# Watch-It-BOTTOM.net
KiCad netlist of a schematic drawn in EAGLE
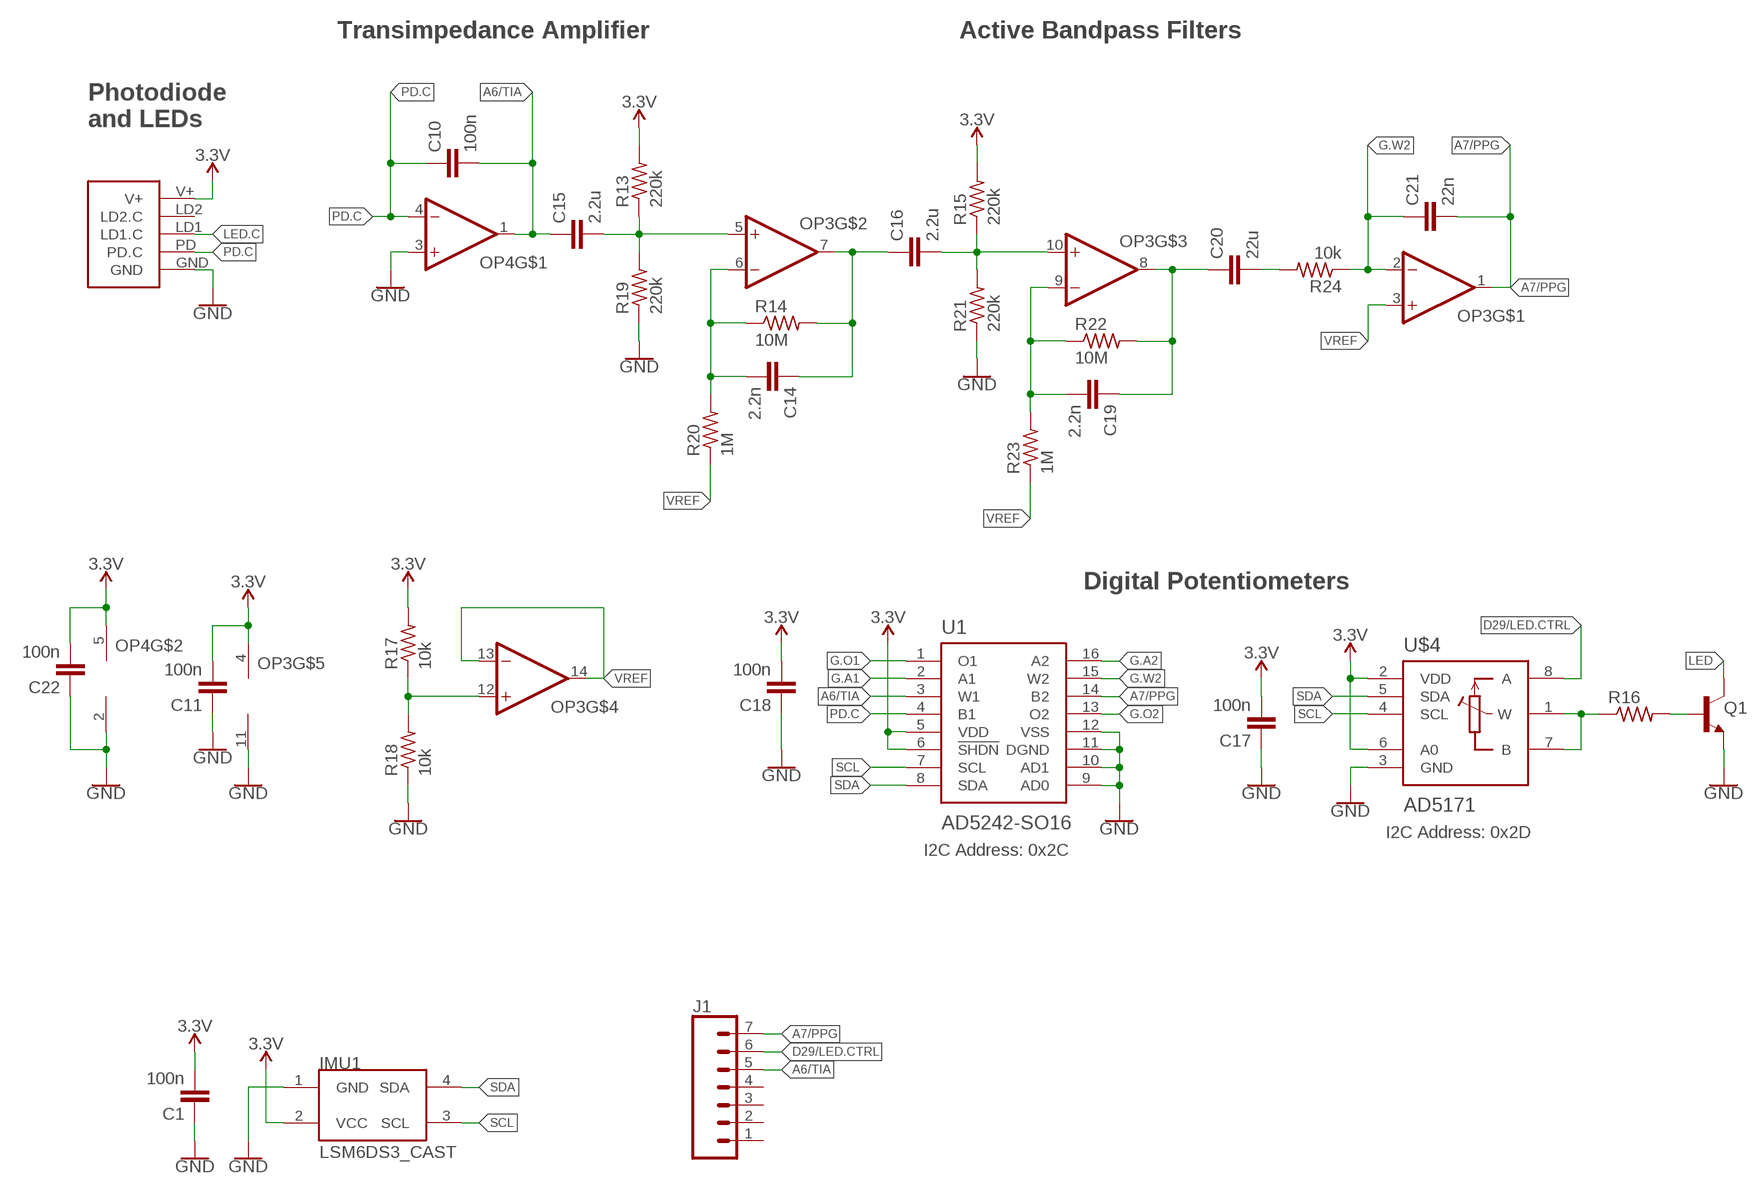
[diagram p0: schematic, sheet 1]

(export (version "E")
  (design (tool "Eeschema 10.0.6"))
  (components
    (comp (ref "C1")
      (value "100n")
      (footprint "eagle-import:C0603")
      (libsource (lib "eagle-import") (part "CAPACITOR0603"))
    )
    (comp (ref "C10")
      (value "100n")
      (footprint "eagle-import:C0603")
      (libsource (lib "eagle-import") (part "CAPACITOR0603"))
    )
    (comp (ref "C11")
      (value "100n")
      (footprint "eagle-import:C0603")
      (libsource (lib "eagle-import") (part "CAPACITOR0603"))
    )
    (comp (ref "C14")
      (value "2.2n")
      (footprint "eagle-import:C0603")
      (libsource (lib "eagle-import") (part "CAPACITOR0603"))
    )
    (comp (ref "C15")
      (value "2.2u")
      (footprint "eagle-import:C0603")
      (libsource (lib "eagle-import") (part "CAPACITOR0603"))
    )
    (comp (ref "C16")
      (value "2.2u")
      (footprint "eagle-import:C0603")
      (libsource (lib "eagle-import") (part "CAPACITOR0603"))
    )
    (comp (ref "C17")
      (value "100n")
      (footprint "eagle-import:C0603")
      (libsource (lib "eagle-import") (part "CAPACITOR0603"))
    )
    (comp (ref "C18")
      (value "100n")
      (footprint "eagle-import:C0603")
      (libsource (lib "eagle-import") (part "CAPACITOR0603"))
    )
    (comp (ref "C19")
      (value "2.2n")
      (footprint "eagle-import:C0603")
      (libsource (lib "eagle-import") (part "CAPACITOR0603"))
    )
    (comp (ref "C20")
      (value "22u")
      (footprint "eagle-import:C0603")
      (libsource (lib "eagle-import") (part "CAPACITOR0603"))
    )
    (comp (ref "C21")
      (value "22n")
      (footprint "eagle-import:C0603")
      (libsource (lib "eagle-import") (part "CAPACITOR0603"))
    )
    (comp (ref "C22")
      (value "100n")
      (footprint "eagle-import:C0603")
      (libsource (lib "eagle-import") (part "CAPACITOR0603"))
    )
    (comp (ref "IMU1")
      (value "LSM6DS3_CAST")
      (footprint "eagle-import:LSM6DS3_CAST")
      (libsource (lib "eagle-import") (part "LSM6DS3_CAST"))
    )
    (comp (ref "J1")
      (value "CONN_07")
      (footprint "eagle-import:1X07")
      (libsource (lib "eagle-import") (part "CONN_07"))
    )
    (comp (ref "OP3")
      (value "OP-QUAD-SO14")
      (footprint "eagle-import:SO14")
      (libsource (lib "eagle-import") (part "OP-QUAD-SO14"))
    )
    (comp (ref "OP4")
      (value "OP-SINGLEOT")
      (footprint "eagle-import:SOT23-5")
      (libsource (lib "eagle-import") (part "OP-SINGLEOT"))
    )
    (comp (ref "Q1")
      (value "NPN-GENERIC")
      (footprint "eagle-import:SOT23-3")
      (libsource (lib "eagle-import") (part "NPN-GENERIC"))
    )
    (comp (ref "R13")
      (value "220k")
      (footprint "eagle-import:R0603")
      (libsource (lib "eagle-import") (part "RESISTOR0603"))
    )
    (comp (ref "R14")
      (value "10M")
      (footprint "eagle-import:R0603")
      (libsource (lib "eagle-import") (part "RESISTOR0603"))
    )
    (comp (ref "R15")
      (value "220k")
      (footprint "eagle-import:R0603")
      (libsource (lib "eagle-import") (part "RESISTOR0603"))
    )
    (comp (ref "R16")
      (value "RESISTOR0603")
      (footprint "eagle-import:R0603")
      (libsource (lib "eagle-import") (part "RESISTOR0603"))
    )
    (comp (ref "R17")
      (value "10k")
      (footprint "eagle-import:R0402")
      (libsource (lib "eagle-import") (part "RESISTOR0402"))
    )
    (comp (ref "R18")
      (value "10k")
      (footprint "eagle-import:R0402")
      (libsource (lib "eagle-import") (part "RESISTOR0402"))
    )
    (comp (ref "R19")
      (value "220k")
      (footprint "eagle-import:R0603")
      (libsource (lib "eagle-import") (part "RESISTOR0603"))
    )
    (comp (ref "R20")
      (value "1M")
      (footprint "eagle-import:R0603")
      (libsource (lib "eagle-import") (part "RESISTOR0603"))
    )
    (comp (ref "R21")
      (value "220k")
      (footprint "eagle-import:R0603")
      (libsource (lib "eagle-import") (part "RESISTOR0603"))
    )
    (comp (ref "R22")
      (value "10M")
      (footprint "eagle-import:R0603")
      (libsource (lib "eagle-import") (part "RESISTOR0603"))
    )
    (comp (ref "R23")
      (value "1M")
      (footprint "eagle-import:R0603")
      (libsource (lib "eagle-import") (part "RESISTOR0603"))
    )
    (comp (ref "R24")
      (value "10k")
      (footprint "eagle-import:R0603")
      (libsource (lib "eagle-import") (part "RESISTOR0603"))
    )
    (comp (ref "U$3")
      (value "PPG.MODULE.2")
      (footprint "eagle-import:PPG.MODULE.2")
      (libsource (lib "eagle-import") (part "PPG.MODULE.2"))
    )
    (comp (ref "U$4")
      (value "AD5171")
      (footprint "eagle-import:SOT-23-8")
      (libsource (lib "eagle-import") (part "AD5171"))
    )
    (comp (ref "U1")
      (value "AD5242-SO16")
      (footprint "eagle-import:SO16")
      (libsource (lib "eagle-import") (part "AD5242-SO16"))
    )
  )
  (nets
    (net (code "1") (name "3.3V") (class "Default")
      (node (ref "C1") (pin "2") (pinfunction "2_2") (pintype "passive"))
      (node (ref "C11") (pin "2") (pinfunction "2_2") (pintype "passive"))
      (node (ref "C17") (pin "2") (pinfunction "2_2") (pintype "passive"))
      (node (ref "C18") (pin "2") (pinfunction "2_2") (pintype "passive"))
      (node (ref "C22") (pin "2") (pinfunction "2_2") (pintype "passive"))
      (node (ref "IMU1") (pin "2") (pinfunction "VCC_2") (pintype "bidirectional"))
      (node (ref "OP3") (pin "4") (pinfunction "V+_4") (pintype "power_in"))
      (node (ref "OP4") (pin "5") (pinfunction "V+_5") (pintype "power_in"))
      (node (ref "R13") (pin "2") (pinfunction "2_2") (pintype "passive"))
      (node (ref "R15") (pin "2") (pinfunction "2_2") (pintype "passive"))
      (node (ref "R17") (pin "2") (pinfunction "2_2") (pintype "passive"))
      (node (ref "U$3") (pin "V+") (pinfunction "V+_V+") (pintype "bidirectional"))
      (node (ref "U$4") (pin "2") (pinfunction "VDD_2") (pintype "bidirectional"))
      (node (ref "U$4") (pin "6") (pinfunction "A0_6") (pintype "bidirectional"))
      (node (ref "U1") (pin "5") (pinfunction "VDD_5") (pintype "bidirectional"))
      (node (ref "U1") (pin "6") (pinfunction "~{SHDN}_6") (pintype "bidirectional"))
    )
    (net (code "2") (name "A6{slash}TIA") (class "Default")
      (node (ref "C10") (pin "2") (pinfunction "2_2") (pintype "passive"))
      (node (ref "C15") (pin "1") (pinfunction "1_1") (pintype "passive"))
      (node (ref "J1") (pin "5") (pinfunction "5_5") (pintype "passive"))
      (node (ref "OP4") (pin "1") (pinfunction "OUT_1") (pintype "output"))
      (node (ref "U1") (pin "3") (pinfunction "W1_3") (pintype "bidirectional"))
    )
    (net (code "3") (name "A7{slash}PPG") (class "Default")
      (node (ref "C21") (pin "2") (pinfunction "2_2") (pintype "passive"))
      (node (ref "J1") (pin "7") (pinfunction "7_7") (pintype "passive"))
      (node (ref "OP3") (pin "1") (pinfunction "OUT_1") (pintype "output"))
      (node (ref "U1") (pin "14") (pinfunction "B2_14") (pintype "bidirectional"))
    )
    (net (code "4") (name "D29{slash}LED.CTRL") (class "Default")
      (node (ref "J1") (pin "6") (pinfunction "6_6") (pintype "passive"))
      (node (ref "U$4") (pin "8") (pinfunction "A_8") (pintype "bidirectional"))
    )
    (net (code "5") (name "G.A1") (class "Default")
      (node (ref "U1") (pin "2") (pinfunction "A1_2") (pintype "bidirectional"))
    )
    (net (code "6") (name "G.A2") (class "Default")
      (node (ref "U1") (pin "16") (pinfunction "A2_16") (pintype "bidirectional"))
    )
    (net (code "7") (name "G.O1") (class "Default")
      (node (ref "U1") (pin "1") (pinfunction "O1_1") (pintype "bidirectional"))
    )
    (net (code "8") (name "G.O2") (class "Default")
      (node (ref "U1") (pin "13") (pinfunction "O2_13") (pintype "bidirectional"))
    )
    (net (code "9") (name "G.W2") (class "Default")
      (node (ref "C21") (pin "1") (pinfunction "1_1") (pintype "passive"))
      (node (ref "OP3") (pin "2") (pinfunction "-IN_2") (pintype "input"))
      (node (ref "R24") (pin "1") (pinfunction "1_1") (pintype "passive"))
      (node (ref "U1") (pin "15") (pinfunction "W2_15") (pintype "bidirectional"))
    )
    (net (code "10") (name "GND") (class "Default")
      (node (ref "C1") (pin "1") (pinfunction "1_1") (pintype "passive"))
      (node (ref "C11") (pin "1") (pinfunction "1_1") (pintype "passive"))
      (node (ref "C17") (pin "1") (pinfunction "1_1") (pintype "passive"))
      (node (ref "C18") (pin "1") (pinfunction "1_1") (pintype "passive"))
      (node (ref "C22") (pin "1") (pinfunction "1_1") (pintype "passive"))
      (node (ref "IMU1") (pin "1") (pinfunction "GND_1") (pintype "bidirectional"))
      (node (ref "OP3") (pin "11") (pinfunction "V-_11") (pintype "power_in"))
      (node (ref "OP4") (pin "2") (pinfunction "V-_2") (pintype "power_in"))
      (node (ref "OP4") (pin "3") (pinfunction "+IN_3") (pintype "input"))
      (node (ref "Q1") (pin "2") (pinfunction "E_2") (pintype "passive"))
      (node (ref "R18") (pin "1") (pinfunction "1_1") (pintype "passive"))
      (node (ref "R19") (pin "1") (pinfunction "1_1") (pintype "passive"))
      (node (ref "R21") (pin "1") (pinfunction "1_1") (pintype "passive"))
      (node (ref "U$3") (pin "GND") (pinfunction "GND_GND") (pintype "bidirectional"))
      (node (ref "U$4") (pin "3") (pinfunction "GND_3") (pintype "bidirectional"))
      (node (ref "U1") (pin "10") (pinfunction "AD1_10") (pintype "bidirectional"))
      (node (ref "U1") (pin "11") (pinfunction "DGND_11") (pintype "bidirectional"))
      (node (ref "U1") (pin "12") (pinfunction "VSS_12") (pintype "bidirectional"))
      (node (ref "U1") (pin "9") (pinfunction "AD0_9") (pintype "bidirectional"))
    )
    (net (code "11") (name "LED") (class "Default")
      (node (ref "Q1") (pin "3") (pinfunction "C_3") (pintype "passive"))
    )
    (net (code "12") (name "LED.C") (class "Default")
      (node (ref "U$3") (pin "LD1") (pinfunction "LD1.C_LD1") (pintype "bidirectional"))
    )
    (net (code "13") (name "Net-(C20-Pad2)") (class "Default")
      (node (ref "C20") (pin "2") (pinfunction "2_2") (pintype "passive"))
      (node (ref "R24") (pin "2") (pinfunction "2_2") (pintype "passive"))
    )
    (net (code "14") (name "Net-(OP3B-+IN)") (class "Default")
      (node (ref "C15") (pin "2") (pinfunction "2_2") (pintype "passive"))
      (node (ref "OP3") (pin "5") (pinfunction "+IN_5") (pintype "input"))
      (node (ref "R13") (pin "1") (pinfunction "1_1") (pintype "passive"))
      (node (ref "R19") (pin "2") (pinfunction "2_2") (pintype "passive"))
    )
    (net (code "15") (name "Net-(OP3B--IN)") (class "Default")
      (node (ref "C14") (pin "2") (pinfunction "2_2") (pintype "passive"))
      (node (ref "OP3") (pin "6") (pinfunction "-IN_6") (pintype "input"))
      (node (ref "R14") (pin "1") (pinfunction "1_1") (pintype "passive"))
      (node (ref "R20") (pin "2") (pinfunction "2_2") (pintype "passive"))
    )
    (net (code "16") (name "Net-(OP3B-OUT)") (class "Default")
      (node (ref "C14") (pin "1") (pinfunction "1_1") (pintype "passive"))
      (node (ref "C16") (pin "1") (pinfunction "1_1") (pintype "passive"))
      (node (ref "OP3") (pin "7") (pinfunction "OUT_7") (pintype "output"))
      (node (ref "R14") (pin "2") (pinfunction "2_2") (pintype "passive"))
    )
    (net (code "17") (name "Net-(OP3C-+IN)") (class "Default")
      (node (ref "C16") (pin "2") (pinfunction "2_2") (pintype "passive"))
      (node (ref "OP3") (pin "10") (pinfunction "+IN_10") (pintype "input"))
      (node (ref "R15") (pin "1") (pinfunction "1_1") (pintype "passive"))
      (node (ref "R21") (pin "2") (pinfunction "2_2") (pintype "passive"))
    )
    (net (code "18") (name "Net-(OP3C--IN)") (class "Default")
      (node (ref "C19") (pin "2") (pinfunction "2_2") (pintype "passive"))
      (node (ref "OP3") (pin "9") (pinfunction "-IN_9") (pintype "input"))
      (node (ref "R22") (pin "1") (pinfunction "1_1") (pintype "passive"))
      (node (ref "R23") (pin "2") (pinfunction "2_2") (pintype "passive"))
    )
    (net (code "19") (name "Net-(OP3C-OUT)") (class "Default")
      (node (ref "C19") (pin "1") (pinfunction "1_1") (pintype "passive"))
      (node (ref "C20") (pin "1") (pinfunction "1_1") (pintype "passive"))
      (node (ref "OP3") (pin "8") (pinfunction "OUT_8") (pintype "output"))
      (node (ref "R22") (pin "2") (pinfunction "2_2") (pintype "passive"))
    )
    (net (code "20") (name "Net-(OP3D-+IN)") (class "Default")
      (node (ref "OP3") (pin "12") (pinfunction "+IN_12") (pintype "input"))
      (node (ref "R17") (pin "1") (pinfunction "1_1") (pintype "passive"))
      (node (ref "R18") (pin "2") (pinfunction "2_2") (pintype "passive"))
    )
    (net (code "21") (name "Net-(Q1-B)") (class "Default")
      (node (ref "Q1") (pin "1") (pinfunction "B_1") (pintype "passive"))
      (node (ref "R16") (pin "2") (pinfunction "2_2") (pintype "passive"))
    )
    (net (code "22") (name "Net-(U$4-B)") (class "Default")
      (node (ref "R16") (pin "1") (pinfunction "1_1") (pintype "passive"))
      (node (ref "U$4") (pin "1") (pinfunction "W_1") (pintype "bidirectional"))
      (node (ref "U$4") (pin "7") (pinfunction "B_7") (pintype "bidirectional"))
    )
    (net (code "23") (name "PD.C") (class "Default")
      (node (ref "C10") (pin "1") (pinfunction "1_1") (pintype "passive"))
      (node (ref "OP4") (pin "4") (pinfunction "-IN_4") (pintype "input"))
      (node (ref "U$3") (pin "PD") (pinfunction "PD.C_PD") (pintype "bidirectional"))
      (node (ref "U1") (pin "4") (pinfunction "B1_4") (pintype "bidirectional"))
    )
    (net (code "24") (name "SCL") (class "Default")
      (node (ref "IMU1") (pin "3") (pinfunction "SCL_3") (pintype "bidirectional"))
      (node (ref "U$4") (pin "4") (pinfunction "SCL_4") (pintype "bidirectional"))
      (node (ref "U1") (pin "7") (pinfunction "SCL_7") (pintype "bidirectional"))
    )
    (net (code "25") (name "SDA") (class "Default")
      (node (ref "IMU1") (pin "4") (pinfunction "SDA_4") (pintype "bidirectional"))
      (node (ref "U$4") (pin "5") (pinfunction "SDA_5") (pintype "bidirectional"))
      (node (ref "U1") (pin "8") (pinfunction "SDA_8") (pintype "bidirectional"))
    )
    (net (code "26") (name "VREF") (class "Default")
      (node (ref "OP3") (pin "13") (pinfunction "-IN_13") (pintype "input"))
      (node (ref "OP3") (pin "14") (pinfunction "OUT_14") (pintype "output"))
      (node (ref "OP3") (pin "3") (pinfunction "+IN_3") (pintype "input"))
      (node (ref "R20") (pin "1") (pinfunction "1_1") (pintype "passive"))
      (node (ref "R23") (pin "1") (pinfunction "1_1") (pintype "passive"))
    )
    (net (code "27") (name "unconnected-(J1-Pad1)") (class "Default")
      (node (ref "J1") (pin "1") (pinfunction "1_1") (pintype "passive"))
    )
    (net (code "28") (name "unconnected-(J1-Pad2)") (class "Default")
      (node (ref "J1") (pin "2") (pinfunction "2_2") (pintype "passive"))
    )
    (net (code "29") (name "unconnected-(J1-Pad3)") (class "Default")
      (node (ref "J1") (pin "3") (pinfunction "3_3") (pintype "passive"))
    )
    (net (code "30") (name "unconnected-(J1-Pad4)") (class "Default")
      (node (ref "J1") (pin "4") (pinfunction "4_4") (pintype "passive"))
    )
    (net (code "31") (name "unconnected-(U$3-LD2.C-PadLD2)") (class "Default")
      (node (ref "U$3") (pin "LD2") (pinfunction "LD2.C_LD2") (pintype "bidirectional"))
    )
  )
)
